# design.net
KiCad netlist of a schematic drawn in Altium Designer
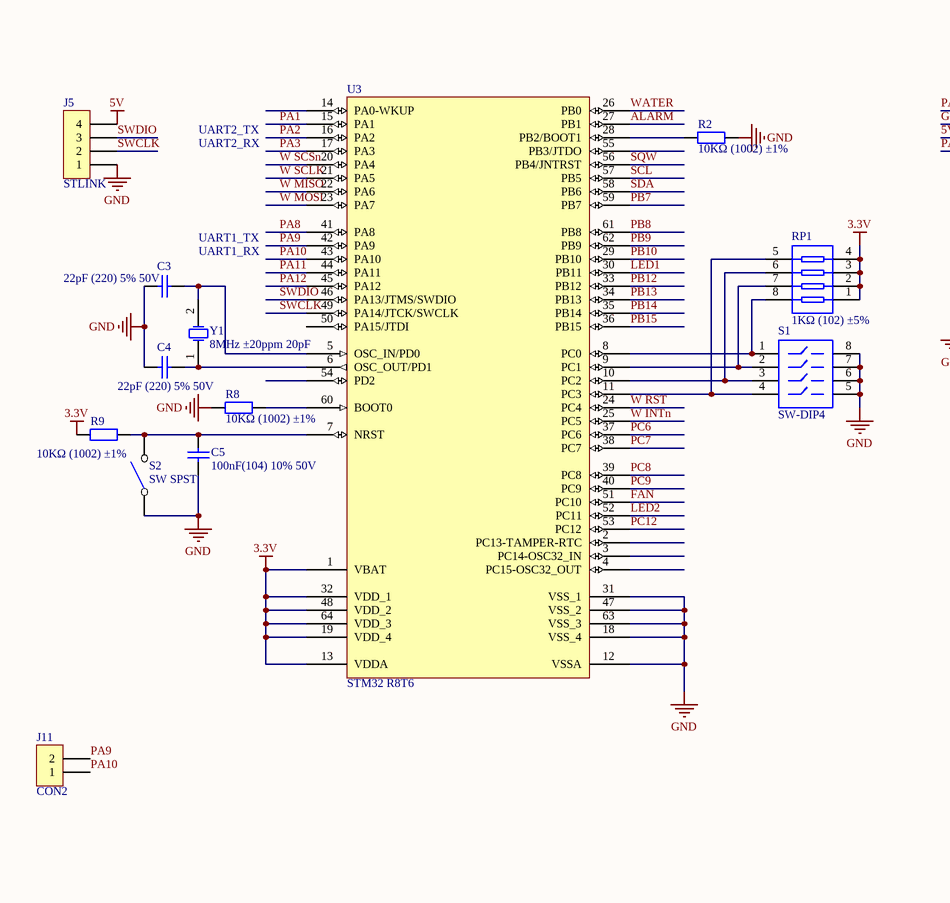
[diagram p0: 控制器.SchDoc, left]
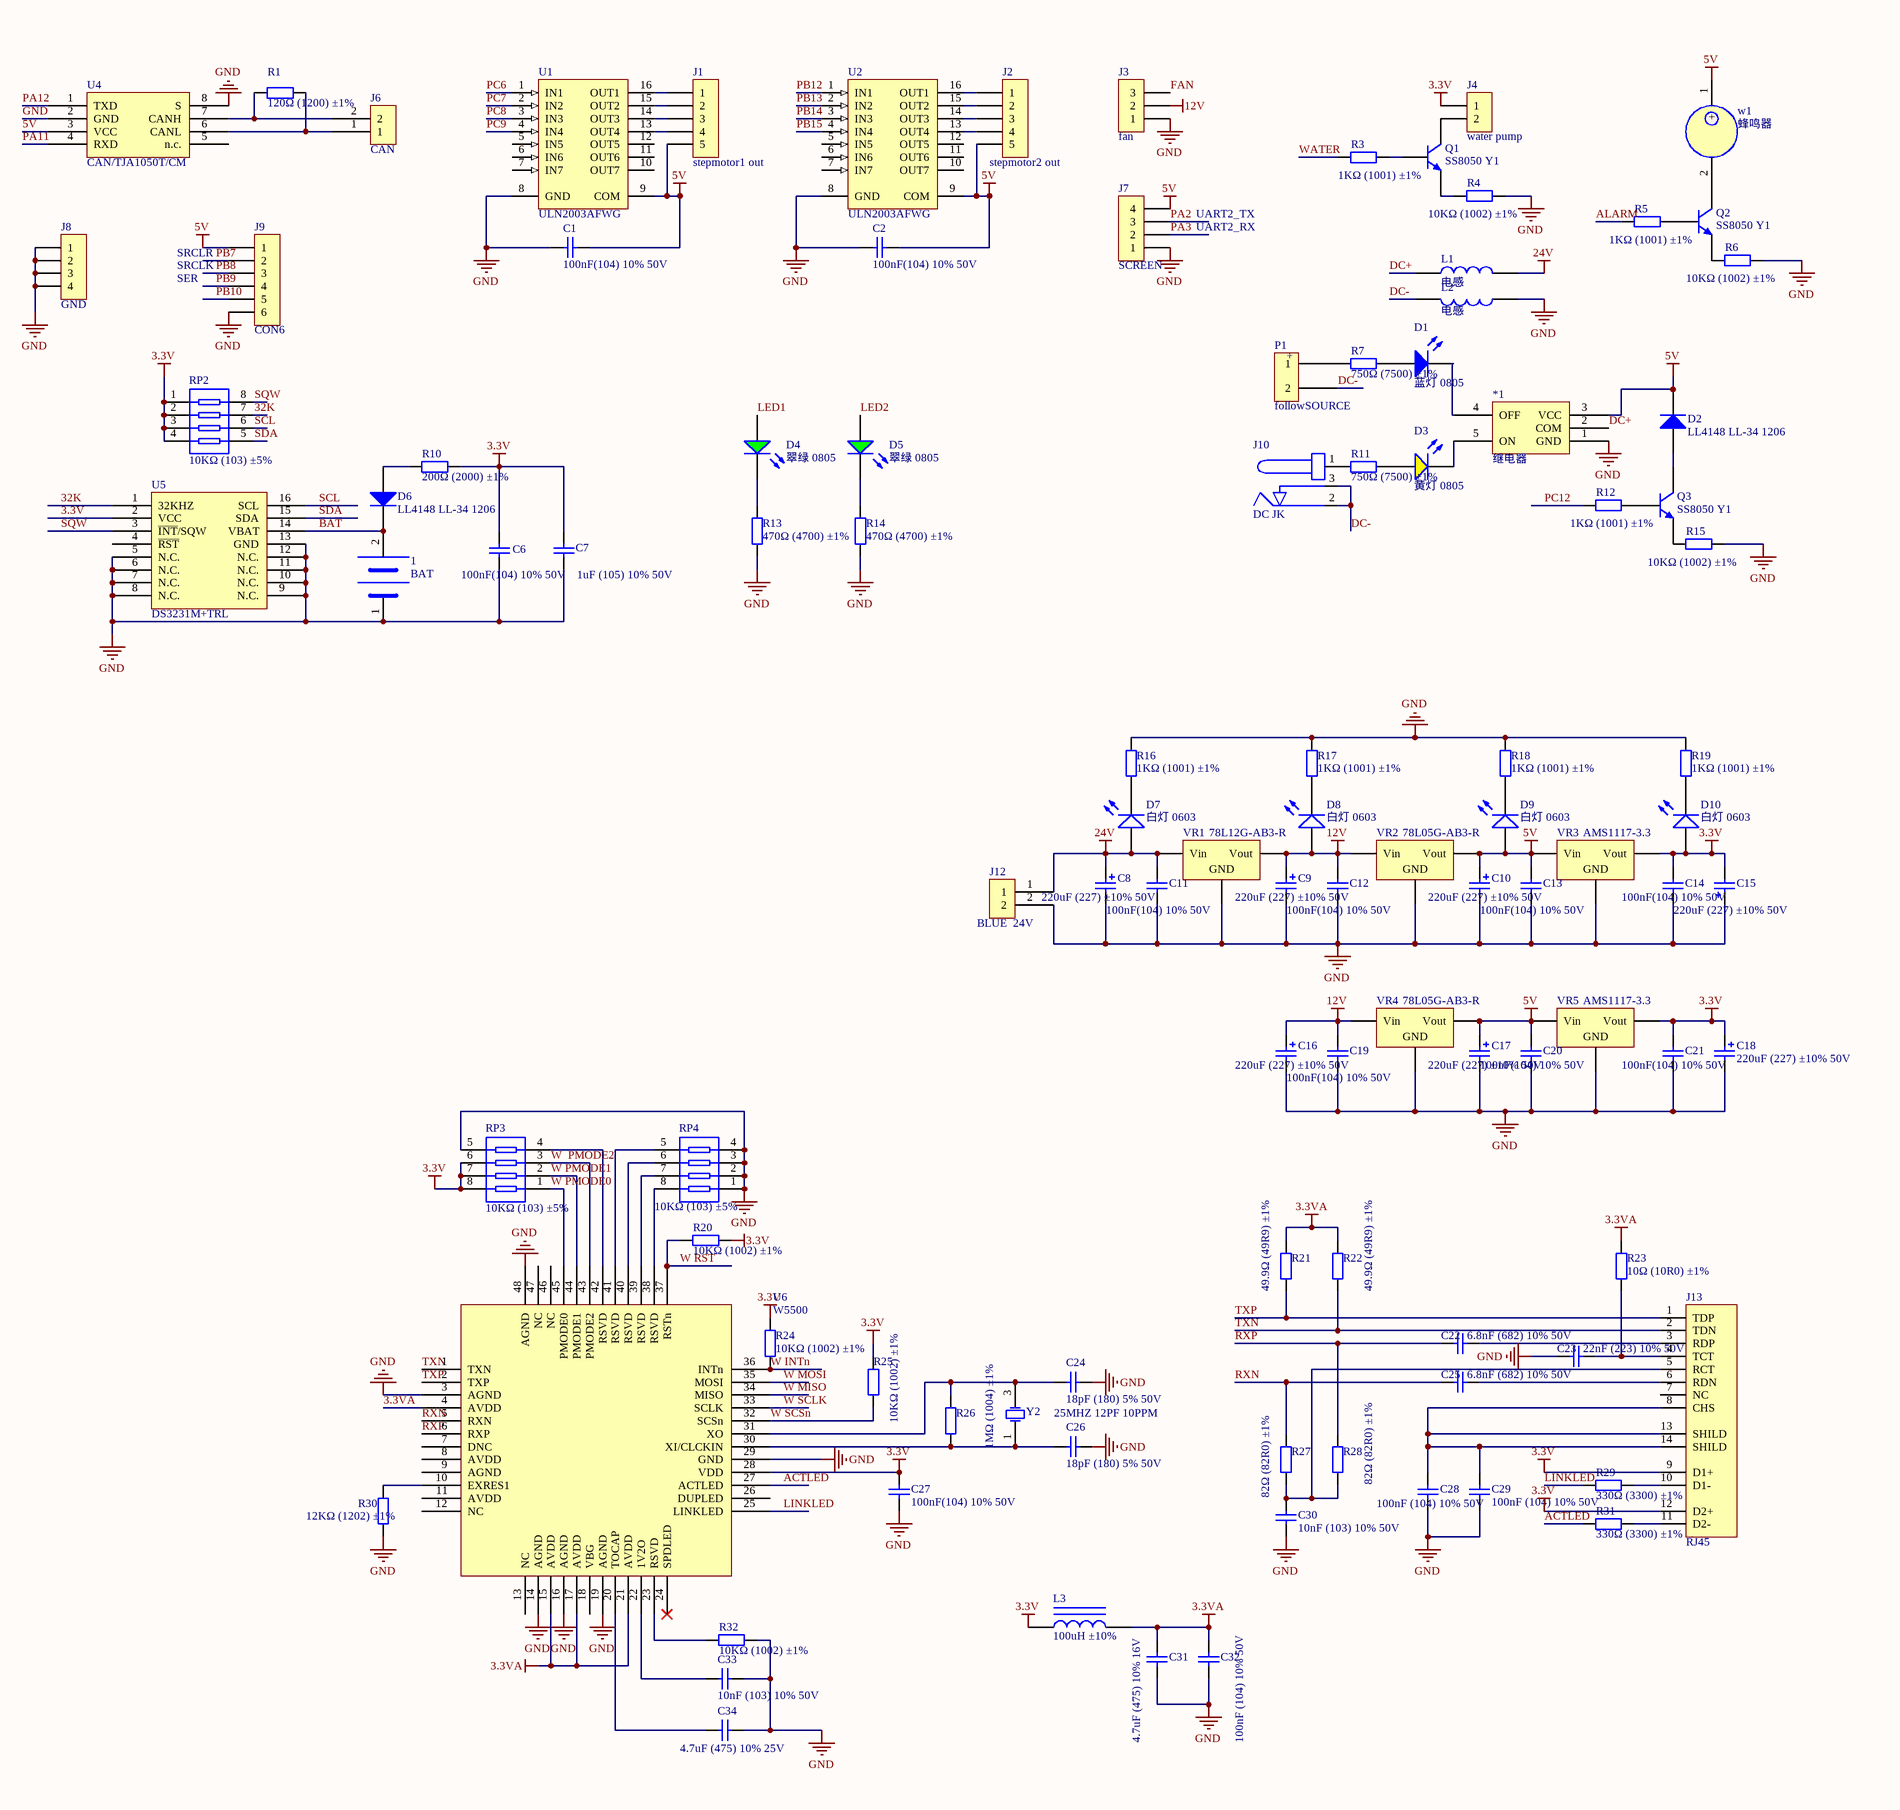
[diagram p1: 控制器.SchDoc, right]

(export (version "E")
  (design (tool "Eeschema 10.0.6"))
  (components
    (comp (ref "*1") (value "继电器") (footprint "RLY-964") (libsource (lib "毕设原理图封装库") (part "继电器")))
    (comp (ref "1") (value "BAT") (footprint "BAT") (libsource (lib "毕设原理图封装库") (part "BAT")))
    (comp (ref "C1")
      (value "100nF(104) 10% 50V")
      (footprint "LC-0805_C")
      (description "贴片电容")
      (libsource (lib "Miscellaneous Devices LC") (part "0805 100nF(104) 10% 50V"))
    )
    (comp (ref "C2")
      (value "100nF(104) 10% 50V")
      (footprint "LC-0805_C")
      (description "贴片电容")
      (libsource (lib "Miscellaneous Devices LC") (part "0805 100nF(104) 10% 50V"))
    )
    (comp (ref "C3")
      (value "22pF (220) 5% 50V")
      (footprint "LC-0805_C")
      (description "贴片电容")
      (libsource (lib "Miscellaneous Devices LC") (part "0805 22pF (220) 5% 50V"))
    )
    (comp (ref "C4")
      (value "22pF (220) 5% 50V")
      (footprint "LC-0805_C")
      (description "贴片电容")
      (libsource (lib "Miscellaneous Devices LC") (part "0805 22pF (220) 5% 50V"))
    )
    (comp (ref "C5")
      (value "100nF(104) 10% 50V")
      (footprint "LC-0805_C")
      (description "贴片电容")
      (libsource (lib "Miscellaneous Devices LC") (part "0805 100nF(104) 10% 50V"))
    )
    (comp (ref "C6")
      (value "100nF(104) 10% 50V")
      (footprint "LC-0805_C")
      (description "贴片电容")
      (libsource (lib "Miscellaneous Devices LC") (part "0805 100nF(104) 10% 50V"))
    )
    (comp (ref "C7")
      (value "1uF (105) 10% 50V")
      (footprint "LC-0805_C")
      (description "贴片电容")
      (libsource (lib "Miscellaneous Devices LC") (part "0805 1uF (105) 10% 50V"))
    )
    (comp (ref "C8")
      (value "220uF (227) ±10% 50V")
      (footprint "LC-CASE-B_3528")
      (description "钽电容")
      (libsource (lib "Miscellaneous Devices LC") (part "3528 100uF (107) 10% 6.3V"))
    )
    (comp (ref "C9")
      (value "220uF (227) ±10% 50V")
      (footprint "LC-CASE-B_3528")
      (description "钽电容")
      (libsource (lib "Miscellaneous Devices LC") (part "3528 100uF (107) 10% 6.3V"))
    )
    (comp (ref "C10")
      (value "220uF (227) ±10% 50V")
      (footprint "LC-CASE-B_3528")
      (description "钽电容")
      (libsource (lib "Miscellaneous Devices LC") (part "3528 100uF (107) 10% 6.3V"))
    )
    (comp (ref "C11")
      (value "100nF(104) 10% 50V")
      (footprint "LC-0805_C")
      (description "贴片电容")
      (libsource (lib "Miscellaneous Devices LC") (part "0805 100nF(104) 10% 50V"))
    )
    (comp (ref "C12")
      (value "100nF(104) 10% 50V")
      (footprint "LC-0805_C")
      (description "贴片电容")
      (libsource (lib "Miscellaneous Devices LC") (part "0805 100nF(104) 10% 50V"))
    )
    (comp (ref "C13")
      (value "100nF(104) 10% 50V")
      (footprint "LC-0805_C")
      (description "贴片电容")
      (libsource (lib "Miscellaneous Devices LC") (part "0805 100nF(104) 10% 50V"))
    )
    (comp (ref "C14")
      (value "100nF(104) 10% 50V")
      (footprint "LC-0805_C")
      (description "贴片电容")
      (libsource (lib "Miscellaneous Devices LC") (part "0805 100nF(104) 10% 50V"))
    )
    (comp (ref "C15")
      (value "220uF (227) ±10% 50V")
      (footprint "LC-CASE-B_3528")
      (description "钽电容")
      (libsource (lib "Miscellaneous Devices LC") (part "3528 100uF (107) 10% 6.3V"))
    )
    (comp (ref "C16")
      (value "220uF (227) ±10% 50V")
      (footprint "LC-CASE-B_3528")
      (description "钽电容")
      (libsource (lib "Miscellaneous Devices LC") (part "3528 100uF (107) 10% 6.3V"))
    )
    (comp (ref "C17")
      (value "220uF (227) ±10% 50V")
      (footprint "LC-CASE-B_3528")
      (description "钽电容")
      (libsource (lib "Miscellaneous Devices LC") (part "3528 100uF (107) 10% 6.3V"))
    )
    (comp (ref "C18")
      (value "220uF (227) ±10% 50V")
      (footprint "LC-CASE-B_3528")
      (description "钽电容")
      (libsource (lib "") (part "3528 100uF (107) 10% 6.3V_1"))
    )
    (comp (ref "C19")
      (value "100nF(104) 10% 50V")
      (footprint "LC-0805_C")
      (description "贴片电容")
      (libsource (lib "Miscellaneous Devices LC") (part "0805 100nF(104) 10% 50V"))
    )
    (comp (ref "C20")
      (value "100nF(104) 10% 50V")
      (footprint "LC-0805_C")
      (description "贴片电容")
      (libsource (lib "Miscellaneous Devices LC") (part "0805 100nF(104) 10% 50V"))
    )
    (comp (ref "C21")
      (value "100nF(104) 10% 50V")
      (footprint "LC-0805_C")
      (description "贴片电容")
      (libsource (lib "Miscellaneous Devices LC") (part "0805 100nF(104) 10% 50V"))
    )
    (comp (ref "C22")
      (value "6.8nF (682) 10% 50V")
      (footprint "LC-0603_C")
      (description "贴片电容")
      (libsource (lib "Miscellaneous Devices LC") (part "0603 6.8nF (682) 10% 50V"))
    )
    (comp (ref "C23")
      (value "22nF (223) 10% 50V")
      (footprint "LC-0603_C")
      (description "贴片电容")
      (libsource (lib "Miscellaneous Devices LC") (part "0603 22nF (223) 10% 50V"))
    )
    (comp (ref "C24")
      (value "18pF (180) 5% 50V")
      (footprint "LC-0805_C")
      (description "贴片电容")
      (libsource (lib "Miscellaneous Devices LC") (part "0805 18pF (180) 5% 50V"))
    )
    (comp (ref "C25")
      (value "6.8nF (682) 10% 50V")
      (footprint "LC-0603_C")
      (description "贴片电容")
      (libsource (lib "Miscellaneous Devices LC") (part "0603 6.8nF (682) 10% 50V"))
    )
    (comp (ref "C26")
      (value "18pF (180) 5% 50V")
      (footprint "LC-0805_C")
      (description "贴片电容")
      (libsource (lib "Miscellaneous Devices LC") (part "0805 18pF (180) 5% 50V"))
    )
    (comp (ref "C27")
      (value "100nF(104) 10% 50V")
      (footprint "LC-0805_C")
      (description "贴片电容")
      (libsource (lib "Miscellaneous Devices LC") (part "0805 100nF(104) 10% 50V"))
    )
    (comp (ref "C28")
      (value "100nF (104) 10% 50V")
      (footprint "LC-0603_C")
      (description "贴片电容")
      (libsource (lib "Miscellaneous Devices LC") (part "0603 100nF (104) 10% 50V"))
    )
    (comp (ref "C29")
      (value "100nF (104) 10% 50V")
      (footprint "LC-0603_C")
      (description "贴片电容")
      (libsource (lib "Miscellaneous Devices LC") (part "0603 100nF (104) 10% 50V"))
    )
    (comp (ref "C30")
      (value "10nF (103) 10% 50V")
      (footprint "LC-0603_C")
      (description "贴片电容")
      (libsource (lib "Miscellaneous Devices LC") (part "0603 10nF (103) 10% 50V"))
    )
    (comp (ref "C31")
      (value "4.7uF (475) 10% 16V")
      (footprint "LC-0603_C")
      (description "贴片电容")
      (libsource (lib "Miscellaneous Devices LC") (part "0603 4.7uF (475) 10% 16V"))
    )
    (comp (ref "C32")
      (value "100nF (104) 10% 50V")
      (footprint "LC-0603_C")
      (description "贴片电容")
      (libsource (lib "Miscellaneous Devices LC") (part "0603 100nF (104) 10% 50V"))
    )
    (comp (ref "C33")
      (value "10nF (103) 10% 50V")
      (footprint "LC-0805_C")
      (description "贴片电容")
      (libsource (lib "Miscellaneous Devices LC") (part "0805 10nF (103) 10% 50V"))
    )
    (comp (ref "C34")
      (value "4.7uF (475) 10% 25V")
      (footprint "LC-0805_C")
      (description "贴片电容")
      (libsource (lib "Miscellaneous Devices LC") (part "0805 4.7uF (475) 10% 25V"))
    )
    (comp (ref "D1")
      (value "蓝灯 0805")
      (footprint "LC-0805_LED_S1")
      (description "发光二极管")
      (libsource (lib "Miscellaneous Devices LC") (part "0805 蓝灯"))
    )
    (comp (ref "D2")
      (value "LL4148 LL-34 1206")
      (footprint "LC-LL-34")
      (description "开关二极管")
      (libsource (lib "Miscellaneous Devices LC") (part "LL-34 LL4148 LL-34 1206"))
    )
    (comp (ref "D3")
      (value "黄灯 0805")
      (footprint "LC-0805_LED_S1")
      (description "发光二极管")
      (libsource (lib "Miscellaneous Devices LC") (part "0805 黄灯"))
    )
    (comp (ref "D4")
      (value "翠绿 0805")
      (footprint "LC-0805_LED_S1")
      (description "发光二极管")
      (libsource (lib "Miscellaneous Devices LC") (part "0805 翠绿"))
    )
    (comp (ref "D5")
      (value "翠绿 0805")
      (footprint "LC-0805_LED_S1")
      (description "发光二极管")
      (libsource (lib "Miscellaneous Devices LC") (part "0805 翠绿"))
    )
    (comp (ref "D6")
      (value "LL4148 LL-34 1206")
      (footprint "LC-LL-34")
      (description "开关二极管")
      (libsource (lib "Miscellaneous Devices LC") (part "LL-34 LL4148 LL-34 1206"))
    )
    (comp (ref "D7")
      (value "白灯 0603")
      (footprint "LC-0603_LED_S1")
      (description "发光二极管")
      (libsource (lib "Miscellaneous Devices LC") (part "0603 白灯"))
    )
    (comp (ref "D8")
      (value "白灯 0603")
      (footprint "LC-0603_LED_S1")
      (description "发光二极管")
      (libsource (lib "Miscellaneous Devices LC") (part "0603 白灯"))
    )
    (comp (ref "D9")
      (value "白灯 0603")
      (footprint "LC-0603_LED_S1")
      (description "发光二极管")
      (libsource (lib "Miscellaneous Devices LC") (part "0603 白灯"))
    )
    (comp (ref "D10")
      (value "白灯 0603")
      (footprint "LC-0603_LED_S1")
      (description "发光二极管")
      (libsource (lib "Miscellaneous Devices LC") (part "0603 白灯"))
    )
    (comp (ref "J1") (value "stepmotor1 out") (footprint "防反插乘5") (libsource (lib "原理图封装库") (part "CON5")))
    (comp (ref "J2") (value "stepmotor2 out") (footprint "防反插乘5") (libsource (lib "原理图封装库") (part "CON5")))
    (comp (ref "J3") (value "fan") (footprint "SIP3") (libsource (lib "原理图封装库") (part "CON3")))
    (comp (ref "J4") (value "water pump") (footprint "SIP2") (libsource (lib "原理图封装库") (part "CON2")))
    (comp (ref "J5") (value "STLINK") (footprint "SIP4") (libsource (lib "毕设原理图封装库") (part "CON4")))
    (comp (ref "J6") (value "CAN") (footprint "蓝端子") (libsource (lib "") (part "蓝端子_2")))
    (comp (ref "J7") (value "SCREEN") (footprint "SIP4") (libsource (lib "毕设原理图封装库") (part "CON4")))
    (comp (ref "J8") (value "GND") (footprint "SIP4") (libsource (lib "") (part "CON4_1")))
    (comp (ref "J9") (value "CON6") (footprint "SIP6") (libsource (lib "毕设原理图封装库") (part "CON6")))
    (comp (ref "J10") (value "DC JK") (footprint "DC") (libsource (lib "Backup of 耳机座") (part "DC JK")))
    (comp (ref "J11") (value "CON2") (footprint "SIP2") (libsource (lib "毕设原理图封装库") (part "CON2")))
    (comp (ref "J12") (value "BLUE  24V") (footprint "蓝端子") (libsource (lib "") (part "蓝端子_1")))
    (comp (ref "J13") (value "RJ45") (footprint "RJ-45_GBE") (libsource (lib "毕设原理图封装库") (part "RJ45")))
    (comp (ref "L1") (value "电感") (libsource (lib "毕设原理图封装库") (part "电感")))
    (comp (ref "L2") (value "电感") (libsource (lib "毕设原理图封装库") (part "电感")))
    (comp (ref "L3")
      (value "100uH ±10%")
      (footprint "LC-0805_L")
      (description "贴片电感")
      (libsource (lib "Miscellaneous Devices LC") (part "0805 100uH 10%"))
    )
    (comp (ref "P1") (value "followSOURCE") (footprint "蓝端子") (libsource (lib "毕设原理图封装库") (part "蓝端子")))
    (comp (ref "Q1")
      (value "SS8050 Y1")
      (footprint "LC-SOT-23(SOT-23-3)")
      (description "三极管")
      (libsource (lib "Miscellaneous Devices LC") (part "SOT-23 SS8050 Y1"))
    )
    (comp (ref "Q2")
      (value "SS8050 Y1")
      (footprint "LC-SOT-23(SOT-23-3)")
      (description "三极管")
      (libsource (lib "Miscellaneous Devices LC") (part "SOT-23 SS8050 Y1"))
    )
    (comp (ref "Q3")
      (value "SS8050 Y1")
      (footprint "LC-SOT-23(SOT-23-3)")
      (description "三极管")
      (libsource (lib "Miscellaneous Devices LC") (part "SOT-23 SS8050 Y1"))
    )
    (comp (ref "R1")
      (value "120Ω (1200) ±1%")
      (footprint "LC-0805_R")
      (description "贴片电阻")
      (libsource (lib "Miscellaneous Devices LC") (part "0805 120Ω (1200) 1%"))
    )
    (comp (ref "R2")
      (value "10KΩ (1002) ±1%")
      (footprint "LC-0805_R")
      (description "贴片电阻")
      (libsource (lib "Miscellaneous Devices LC") (part "0805 10KΩ (1002) 1%"))
    )
    (comp (ref "R3")
      (value "1KΩ (1001) ±1%")
      (footprint "LC-0805_R")
      (description "贴片电阻")
      (libsource (lib "Miscellaneous Devices LC") (part "0805 1KΩ (1001) 1%"))
    )
    (comp (ref "R4")
      (value "10KΩ (1002) ±1%")
      (footprint "LC-0805_R")
      (description "贴片电阻")
      (libsource (lib "Miscellaneous Devices LC") (part "0805 10KΩ (1002) 1%"))
    )
    (comp (ref "R5")
      (value "1KΩ (1001) ±1%")
      (footprint "LC-0805_R")
      (description "贴片电阻")
      (libsource (lib "Miscellaneous Devices LC") (part "0805 1KΩ (1001) 1%"))
    )
    (comp (ref "R6")
      (value "10KΩ (1002) ±1%")
      (footprint "LC-0805_R")
      (description "贴片电阻")
      (libsource (lib "Miscellaneous Devices LC") (part "0805 10KΩ (1002) 1%"))
    )
    (comp (ref "R7")
      (value "750Ω (7500) ±1%")
      (footprint "LC-0805_R")
      (description "贴片电阻")
      (libsource (lib "Miscellaneous Devices LC") (part "0805 750Ω (7500) 1%"))
    )
    (comp (ref "R8")
      (value "10KΩ (1002) ±1%")
      (footprint "LC-0805_R")
      (description "贴片电阻")
      (libsource (lib "Miscellaneous Devices LC") (part "0805 10KΩ (1002) 1%"))
    )
    (comp (ref "R9")
      (value "10KΩ (1002) ±1%")
      (footprint "LC-0805_R")
      (description "贴片电阻")
      (libsource (lib "Miscellaneous Devices LC") (part "0805 10KΩ (1002) 1%"))
    )
    (comp (ref "R10")
      (value "200Ω (2000) ±1%")
      (footprint "LC-0805_R")
      (description "贴片电阻")
      (libsource (lib "Miscellaneous Devices LC") (part "0805 200Ω (2000) 1%"))
    )
    (comp (ref "R11")
      (value "750Ω (7500) ±1%")
      (footprint "LC-0805_R")
      (description "贴片电阻")
      (libsource (lib "Miscellaneous Devices LC") (part "0805 750Ω (7500) 1%"))
    )
    (comp (ref "R12")
      (value "1KΩ (1001) ±1%")
      (footprint "LC-0805_R")
      (description "贴片电阻")
      (libsource (lib "Miscellaneous Devices LC") (part "0805 1KΩ (1001) 1%"))
    )
    (comp (ref "R13")
      (value "470Ω (4700) ±1%")
      (footprint "LC-0805_R")
      (description "贴片电阻")
      (libsource (lib "Miscellaneous Devices LC") (part "0805 470Ω (4700) 1%"))
    )
    (comp (ref "R14")
      (value "470Ω (4700) ±1%")
      (footprint "LC-0805_R")
      (description "贴片电阻")
      (libsource (lib "Miscellaneous Devices LC") (part "0805 470Ω (4700) 1%"))
    )
    (comp (ref "R15")
      (value "10KΩ (1002) ±1%")
      (footprint "LC-0805_R")
      (description "贴片电阻")
      (libsource (lib "Miscellaneous Devices LC") (part "0805 10KΩ (1002) 1%"))
    )
    (comp (ref "R16")
      (value "1KΩ (1001) ±1%")
      (footprint "LC-0603_R")
      (description "贴片电阻")
      (libsource (lib "Miscellaneous Devices LC") (part "0603 1KΩ (1001) 1%"))
    )
    (comp (ref "R17")
      (value "1KΩ (1001) ±1%")
      (footprint "LC-0603_R")
      (description "贴片电阻")
      (libsource (lib "Miscellaneous Devices LC") (part "0603 1KΩ (1001) 1%"))
    )
    (comp (ref "R18")
      (value "1KΩ (1001) ±1%")
      (footprint "LC-0603_R")
      (description "贴片电阻")
      (libsource (lib "Miscellaneous Devices LC") (part "0603 1KΩ (1001) 1%"))
    )
    (comp (ref "R19")
      (value "1KΩ (1001) ±1%")
      (footprint "LC-0603_R")
      (description "贴片电阻")
      (libsource (lib "Miscellaneous Devices LC") (part "0603 1KΩ (1001) 1%"))
    )
    (comp (ref "R20")
      (value "10KΩ (1002) ±1%")
      (footprint "LC-0805_R")
      (description "贴片电阻")
      (libsource (lib "Miscellaneous Devices LC") (part "0805 10KΩ (1002) 1%"))
    )
    (comp (ref "R21")
      (value "49.9Ω (49R9) ±1%")
      (footprint "LC-0603_R")
      (description "贴片电阻")
      (libsource (lib "Miscellaneous Devices LC") (part "0603 49.9Ω (49R9) 1%"))
    )
    (comp (ref "R22")
      (value "49.9Ω (49R9) ±1%")
      (footprint "LC-0603_R")
      (description "贴片电阻")
      (libsource (lib "Miscellaneous Devices LC") (part "0603 49.9Ω (49R9) 1%"))
    )
    (comp (ref "R23")
      (value "10Ω (10R0) ±1%")
      (footprint "LC-0805_R")
      (description "贴片电阻")
      (libsource (lib "Miscellaneous Devices LC") (part "0805 10Ω (10R0) 1%"))
    )
    (comp (ref "R24")
      (value "10KΩ (1002) ±1%")
      (footprint "LC-0805_R")
      (description "贴片电阻")
      (libsource (lib "") (part "0805 10KΩ (1002) 1%_1"))
    )
    (comp (ref "R25")
      (value "10KΩ (1002) ±1%")
      (footprint "LC-0805_R")
      (description "贴片电阻")
      (libsource (lib "") (part "0805 10KΩ (1002) 1%_1"))
    )
    (comp (ref "R26")
      (value "1MΩ (1004) ±1%")
      (footprint "LC-0805_R")
      (description "贴片电阻")
      (libsource (lib "Miscellaneous Devices LC") (part "0805 1MΩ (1004) 1%"))
    )
    (comp (ref "R27")
      (value "82Ω (82R0) ±1%")
      (footprint "LC-0603_R")
      (description "贴片电阻")
      (libsource (lib "Miscellaneous Devices LC") (part "0603 82Ω (82R0) 1%"))
    )
    (comp (ref "R28")
      (value "82Ω (82R0) ±1%")
      (footprint "LC-0603_R")
      (description "贴片电阻")
      (libsource (lib "Miscellaneous Devices LC") (part "0603 82Ω (82R0) 1%"))
    )
    (comp (ref "R29")
      (value "330Ω (3300) ±1%")
      (footprint "LC-0603_R")
      (description "贴片电阻")
      (libsource (lib "Miscellaneous Devices LC") (part "0603 330Ω (3300) 1%"))
    )
    (comp (ref "R30")
      (value "12KΩ (1202) ±1%")
      (footprint "LC-0805_R")
      (description "贴片电阻")
      (libsource (lib "Miscellaneous Devices LC") (part "0805 12KΩ (1202) 1%"))
    )
    (comp (ref "R31")
      (value "330Ω (3300) ±1%")
      (footprint "LC-0603_R")
      (description "贴片电阻")
      (libsource (lib "Miscellaneous Devices LC") (part "0603 330Ω (3300) 1%"))
    )
    (comp (ref "R32")
      (value "10KΩ (1002) ±1%")
      (footprint "LC-0805_R")
      (description "贴片电阻")
      (libsource (lib "Miscellaneous Devices LC") (part "0805 10KΩ (1002) 1%"))
    )
    (comp (ref "RP1")
      (value "1KΩ (102) ±5%")
      (footprint "LC-0603_Rx4")
      (description "贴片排阻")
      (libsource (lib "Miscellaneous Devices LC") (part "0603*4  1KΩ (102) 5%"))
    )
    (comp (ref "RP2")
      (value "10KΩ (103) ±5%")
      (footprint "LC-0603_Rx4")
      (description "贴片排阻")
      (libsource (lib "Miscellaneous Devices LC") (part "0603*4  10KΩ (103) 5%"))
    )
    (comp (ref "RP3")
      (value "10KΩ (103) ±5%")
      (footprint "LC-0603_Rx4")
      (description "贴片排阻")
      (libsource (lib "Miscellaneous Devices LC") (part "0603*4  10KΩ (103) 5%"))
    )
    (comp (ref "RP4")
      (value "10KΩ (103) ±5%")
      (footprint "LC-0603_Rx4")
      (description "贴片排阻")
      (libsource (lib "Miscellaneous Devices LC") (part "0603*4  10KΩ (103) 5%"))
    )
    (comp (ref "S1")
      (value "SW-DIP4")
      (footprint "4位拨码开关")
      (description "4位拨码开关")
      (libsource (lib "毕设原理图封装库") (part "SW-DIP4"))
    )
    (comp (ref "S2")
      (value "SW SPST")
      (footprint "单片机小按键")
      (description "单刀单掷开关")
      (libsource (lib "毕设原理图封装库") (part "SW SPST"))
    )
    (comp (ref "U1")
      (value "ULN2003AFWG")
      (footprint "LC-SOIC-16_150mil")
      (description "大电流驱动")
      (libsource (lib "Miscellaneous Devices LC") (part "ULN2003AFWG"))
    )
    (comp (ref "U2")
      (value "ULN2003AFWG")
      (footprint "LC-SOIC-16_150mil")
      (description "大电流驱动")
      (libsource (lib "Miscellaneous Devices LC") (part "ULN2003AFWG"))
    )
    (comp (ref "U3")
      (value "STM32 R8T6")
      (footprint "LC-LQFP-64_10x10x05P")
      (libsource (lib "毕设原理图封装库") (part "STM32 R8T6"))
    )
    (comp (ref "U4")
      (value "CAN/TJA1050T/CM")
      (footprint "LC-SOIC-8_150mil")
      (description "CAN")
      (libsource (lib "Miscellaneous Devices LC") (part "CAN/TJA1050T/CM"))
    )
    (comp (ref "U5")
      (value "DS3231M+TRL")
      (footprint "LC-SOIC-16_300mil")
      (description "实时时钟")
      (libsource (lib "Miscellaneous Devices LC") (part "DS3231M+TRL"))
    )
    (comp (ref "U6")
      (value "W5500")
      (footprint "LC-LQFP-48_7x7x05P")
      (description "以太网")
      (libsource (lib "Miscellaneous Devices LC") (part "W5500"))
    )
    (comp (ref "VR1")
      (value "78L12G-AB3-R")
      (footprint "LC-SOT-89(SOT-89-3)")
      (description "低压差线性稳压(LDO)")
      (libsource (lib "Miscellaneous Devices LC") (part "SOT-89 78L12G-AB3-R"))
    )
    (comp (ref "VR2")
      (value "78L05G-AB3-R")
      (footprint "LC-SOT-89(SOT-89-3)")
      (description "低压差线性稳压(LDO)")
      (libsource (lib "Miscellaneous Devices LC") (part "SOT-89 78L05G-AB3-R"))
    )
    (comp (ref "VR3")
      (value "AMS1117-3.3")
      (footprint "LC-SOT-223")
      (description "低压差线性稳压(LDO)")
      (libsource (lib "Miscellaneous Devices LC") (part "SOT-223 AMS1117-3.3"))
    )
    (comp (ref "VR4")
      (value "78L05G-AB3-R")
      (footprint "LC-SOT-89(SOT-89-3)")
      (description "低压差线性稳压(LDO)")
      (libsource (lib "Miscellaneous Devices LC") (part "SOT-89 78L05G-AB3-R"))
    )
    (comp (ref "VR5")
      (value "AMS1117-3.3")
      (footprint "LC-SOT-223")
      (description "低压差线性稳压(LDO)")
      (libsource (lib "Miscellaneous Devices LC") (part "SOT-223 AMS1117-3.3"))
    )
    (comp (ref "w1") (value "蜂鸣器") (footprint "蜂鸣器") (libsource (lib "毕设原理图封装库") (part "蜂鸣器")))
    (comp (ref "Y1")
      (value "8MHz ±20ppm 20pF")
      (footprint "LC-SMD-5032_2P")
      (description "贴片晶振")
      (libsource (lib "Miscellaneous Devices LC") (part "SMD-5032_2P 8MHz 20ppm 20pF"))
    )
    (comp (ref "Y2")
      (value "25MHZ 12PF 10PPM")
      (footprint "LC-SMD-3225_4P")
      (description "贴片晶振")
      (libsource (lib "Miscellaneous Devices LC") (part "SMD-3225_4P  25MHZ 12PF 10PPM"))
    )
  )
  (nets
    (net (code "1") (name "/32K") (class "Default")
      (node (ref "RP2") (pin "7") (pinfunction "7_7") (pintype "passive"))
      (node (ref "U5") (pin "1") (pinfunction "32KHZ_1") (pintype "passive"))
    )
    (net (code "2") (name "/ACTLED") (class "Default")
      (node (ref "R31") (pin "1") (pinfunction "1_1") (pintype "passive"))
      (node (ref "U6") (pin "27") (pinfunction "ACTLED_27") (pintype "passive"))
    )
    (net (code "3") (name "/ALARM") (class "Default")
      (node (ref "R5") (pin "1") (pinfunction "1_1") (pintype "passive"))
      (node (ref "U3") (pin "27") (pinfunction "PB1_27") (pintype "bidirectional"))
    )
    (net (code "4") (name "/BAT") (class "Default")
      (node (ref "1") (pin "2") (pinfunction "2_2") (pintype "passive"))
      (node (ref "D6") (pin "2") (pinfunction "K_2") (pintype "passive"))
      (node (ref "U5") (pin "14") (pinfunction "VBAT_14") (pintype "passive"))
    )
    (net (code "5") (name "/DC+") (class "Default")
      (node (ref "*1") (pin "2") (pinfunction "COM_2") (pintype "passive"))
      (node (ref "L1") (pin "1") (pinfunction "1_1") (pintype "passive"))
    )
    (net (code "6") (name "/DC-") (class "Default")
      (node (ref "J10") (pin "2") (pinfunction "GND_2") (pintype "passive"))
      (node (ref "J10") (pin "3") (pinfunction "GND_3") (pintype "passive"))
      (node (ref "L2") (pin "2") (pinfunction "2_2") (pintype "passive"))
      (node (ref "P1") (pin "2") (pinfunction "2_2") (pintype "passive"))
    )
    (net (code "7") (name "/FAN") (class "Default")
      (node (ref "J3") (pin "3") (pinfunction "3_3") (pintype "passive"))
      (node (ref "U3") (pin "51") (pinfunction "PC10_51") (pintype "bidirectional"))
    )
    (net (code "8") (name "/LED1") (class "Default")
      (node (ref "D4") (pin "A") (pinfunction "A_A") (pintype "passive"))
      (node (ref "U3") (pin "30") (pinfunction "PB11_30") (pintype "bidirectional"))
    )
    (net (code "9") (name "/LED2") (class "Default")
      (node (ref "D5") (pin "A") (pinfunction "A_A") (pintype "passive"))
      (node (ref "U3") (pin "52") (pinfunction "PC11_52") (pintype "bidirectional"))
    )
    (net (code "10") (name "/LINKLED") (class "Default")
      (node (ref "R29") (pin "1") (pinfunction "1_1") (pintype "passive"))
      (node (ref "U6") (pin "25") (pinfunction "LINKLED_25") (pintype "passive"))
    )
    (net (code "11") (name "/PA1") (class "Default")
      (node (ref "U3") (pin "15") (pinfunction "PA1_15") (pintype "bidirectional"))
    )
    (net (code "12") (name "/PA2") (class "Default")
      (node (ref "J7") (pin "3") (pinfunction "3_3") (pintype "passive"))
      (node (ref "U3") (pin "16") (pinfunction "PA2_16") (pintype "bidirectional"))
    )
    (net (code "13") (name "/PA3") (class "Default")
      (node (ref "J7") (pin "2") (pinfunction "2_2") (pintype "passive"))
      (node (ref "U3") (pin "17") (pinfunction "PA3_17") (pintype "bidirectional"))
    )
    (net (code "14") (name "/PA8") (class "Default")
      (node (ref "U3") (pin "41") (pinfunction "PA8_41") (pintype "bidirectional"))
    )
    (net (code "15") (name "/PA9") (class "Default")
      (node (ref "J11") (pin "2") (pinfunction "2_2") (pintype "passive"))
      (node (ref "U3") (pin "42") (pinfunction "PA9_42") (pintype "bidirectional"))
    )
    (net (code "16") (name "/PA10") (class "Default")
      (node (ref "J11") (pin "1") (pinfunction "1_1") (pintype "passive"))
      (node (ref "U3") (pin "43") (pinfunction "PA10_43") (pintype "bidirectional"))
    )
    (net (code "17") (name "/PA11") (class "Default")
      (node (ref "U3") (pin "44") (pinfunction "PA11_44") (pintype "bidirectional"))
      (node (ref "U4") (pin "4") (pinfunction "RXD_4") (pintype "passive"))
    )
    (net (code "18") (name "/PA12") (class "Default")
      (node (ref "U3") (pin "45") (pinfunction "PA12_45") (pintype "bidirectional"))
      (node (ref "U4") (pin "1") (pinfunction "TXD_1") (pintype "passive"))
    )
    (net (code "19") (name "/PB7") (class "Default")
      (node (ref "J9") (pin "2") (pinfunction "2_2") (pintype "passive"))
      (node (ref "U3") (pin "59") (pinfunction "PB7_59") (pintype "bidirectional"))
    )
    (net (code "20") (name "/PB8") (class "Default")
      (node (ref "J9") (pin "3") (pinfunction "3_3") (pintype "passive"))
      (node (ref "U3") (pin "61") (pinfunction "PB8_61") (pintype "bidirectional"))
    )
    (net (code "21") (name "/PB9") (class "Default")
      (node (ref "J9") (pin "4") (pinfunction "4_4") (pintype "passive"))
      (node (ref "U3") (pin "62") (pinfunction "PB9_62") (pintype "bidirectional"))
    )
    (net (code "22") (name "/PB10") (class "Default")
      (node (ref "J9") (pin "5") (pinfunction "5_5") (pintype "passive"))
      (node (ref "U3") (pin "29") (pinfunction "PB10_29") (pintype "bidirectional"))
    )
    (net (code "23") (name "/PB12") (class "Default")
      (node (ref "U2") (pin "1") (pinfunction "IN1_1") (pintype "input"))
      (node (ref "U3") (pin "33") (pinfunction "PB12_33") (pintype "bidirectional"))
    )
    (net (code "24") (name "/PB13") (class "Default")
      (node (ref "U2") (pin "2") (pinfunction "IN2_2") (pintype "input"))
      (node (ref "U3") (pin "34") (pinfunction "PB13_34") (pintype "bidirectional"))
    )
    (net (code "25") (name "/PB14") (class "Default")
      (node (ref "U2") (pin "3") (pinfunction "IN3_3") (pintype "input"))
      (node (ref "U3") (pin "35") (pinfunction "PB14_35") (pintype "bidirectional"))
    )
    (net (code "26") (name "/PB15") (class "Default")
      (node (ref "U2") (pin "4") (pinfunction "IN4_4") (pintype "input"))
      (node (ref "U3") (pin "36") (pinfunction "PB15_36") (pintype "bidirectional"))
    )
    (net (code "27") (name "/PC6") (class "Default")
      (node (ref "U1") (pin "1") (pinfunction "IN1_1") (pintype "input"))
      (node (ref "U3") (pin "37") (pinfunction "PC6_37") (pintype "bidirectional"))
    )
    (net (code "28") (name "/PC7") (class "Default")
      (node (ref "U1") (pin "2") (pinfunction "IN2_2") (pintype "input"))
      (node (ref "U3") (pin "38") (pinfunction "PC7_38") (pintype "bidirectional"))
    )
    (net (code "29") (name "/PC8") (class "Default")
      (node (ref "U1") (pin "3") (pinfunction "IN3_3") (pintype "input"))
      (node (ref "U3") (pin "39") (pinfunction "PC8_39") (pintype "bidirectional"))
    )
    (net (code "30") (name "/PC9") (class "Default")
      (node (ref "U1") (pin "4") (pinfunction "IN4_4") (pintype "input"))
      (node (ref "U3") (pin "40") (pinfunction "PC9_40") (pintype "bidirectional"))
    )
    (net (code "31") (name "/PC12") (class "Default")
      (node (ref "R12") (pin "1") (pinfunction "1_1") (pintype "passive"))
      (node (ref "U3") (pin "53") (pinfunction "PC12_53") (pintype "bidirectional"))
    )
    (net (code "32") (name "/RXN") (class "Default")
      (node (ref "C25") (pin "1") (pinfunction "1_1") (pintype "passive"))
      (node (ref "R27") (pin "2") (pinfunction "2_2") (pintype "passive"))
      (node (ref "U6") (pin "5") (pinfunction "RXN_5") (pintype "passive"))
    )
    (net (code "33") (name "/RXP") (class "Default")
      (node (ref "C22") (pin "1") (pinfunction "1_1") (pintype "passive"))
      (node (ref "R28") (pin "2") (pinfunction "2_2") (pintype "passive"))
      (node (ref "U6") (pin "6") (pinfunction "RXP_6") (pintype "passive"))
    )
    (net (code "34") (name "/SCL") (class "Default")
      (node (ref "RP2") (pin "6") (pinfunction "6_6") (pintype "passive"))
      (node (ref "U3") (pin "57") (pinfunction "PB5_57") (pintype "bidirectional"))
      (node (ref "U5") (pin "16") (pinfunction "SCL_16") (pintype "passive"))
    )
    (net (code "35") (name "/SDA") (class "Default")
      (node (ref "RP2") (pin "5") (pinfunction "5_5") (pintype "passive"))
      (node (ref "U3") (pin "58") (pinfunction "PB6_58") (pintype "bidirectional"))
      (node (ref "U5") (pin "15") (pinfunction "SDA_15") (pintype "passive"))
    )
    (net (code "36") (name "/SQW") (class "Default")
      (node (ref "RP2") (pin "8") (pinfunction "8_8") (pintype "passive"))
      (node (ref "U3") (pin "56") (pinfunction "PB4/JNTRST_56") (pintype "bidirectional"))
      (node (ref "U5") (pin "3") (pinfunction "~{INT}/SQW_3") (pintype "passive"))
    )
    (net (code "37") (name "/SWCLK") (class "Default")
      (node (ref "J5") (pin "2") (pinfunction "2_2") (pintype "passive"))
      (node (ref "U3") (pin "49") (pinfunction "PA14/JTCK/SWCLK_49") (pintype "bidirectional"))
    )
    (net (code "38") (name "/SWDIO") (class "Default")
      (node (ref "J5") (pin "3") (pinfunction "3_3") (pintype "passive"))
      (node (ref "U3") (pin "46") (pinfunction "PA13/JTMS/SWDIO_46") (pintype "bidirectional"))
    )
    (net (code "39") (name "/TXN") (class "Default")
      (node (ref "J13") (pin "2") (pinfunction "TDN_2") (pintype "passive"))
      (node (ref "R22") (pin "1") (pinfunction "1_1") (pintype "passive"))
      (node (ref "U6") (pin "1") (pinfunction "TXN_1") (pintype "passive"))
    )
    (net (code "40") (name "/TXP") (class "Default")
      (node (ref "J13") (pin "1") (pinfunction "TDP_1") (pintype "passive"))
      (node (ref "R21") (pin "1") (pinfunction "1_1") (pintype "passive"))
      (node (ref "U6") (pin "2") (pinfunction "TXP_2") (pintype "passive"))
    )
    (net (code "41") (name "/W  PMODE2") (class "Default")
      (node (ref "RP3") (pin "3") (pinfunction "3_3") (pintype "passive"))
      (node (ref "U6") (pin "43") (pinfunction "PMODE2_43") (pintype "passive"))
    )
    (net (code "42") (name "/W INTn") (class "Default")
      (node (ref "R24") (pin "1") (pinfunction "1_1") (pintype "passive"))
      (node (ref "U3") (pin "25") (pinfunction "PC5_25") (pintype "bidirectional"))
      (node (ref "U6") (pin "36") (pinfunction "INTn_36") (pintype "passive"))
    )
    (net (code "43") (name "/W MISO") (class "Default")
      (node (ref "U3") (pin "22") (pinfunction "PA6_22") (pintype "bidirectional"))
      (node (ref "U6") (pin "34") (pinfunction "MISO_34") (pintype "passive"))
    )
    (net (code "44") (name "/W MOSI") (class "Default")
      (node (ref "U3") (pin "23") (pinfunction "PA7_23") (pintype "bidirectional"))
      (node (ref "U6") (pin "35") (pinfunction "MOSI_35") (pintype "passive"))
    )
    (net (code "45") (name "/W PMODE0") (class "Default")
      (node (ref "RP3") (pin "1") (pinfunction "1_1") (pintype "passive"))
      (node (ref "U6") (pin "45") (pinfunction "PMODE0_45") (pintype "passive"))
    )
    (net (code "46") (name "/W PMODE1") (class "Default")
      (node (ref "RP3") (pin "2") (pinfunction "2_2") (pintype "passive"))
      (node (ref "U6") (pin "44") (pinfunction "PMODE1_44") (pintype "passive"))
    )
    (net (code "47") (name "/W RST") (class "Default")
      (node (ref "R20") (pin "1") (pinfunction "1_1") (pintype "passive"))
      (node (ref "U3") (pin "24") (pinfunction "PC4_24") (pintype "bidirectional"))
      (node (ref "U6") (pin "37") (pinfunction "RSTn_37") (pintype "passive"))
    )
    (net (code "48") (name "/W SCLK") (class "Default")
      (node (ref "U3") (pin "21") (pinfunction "PA5_21") (pintype "bidirectional"))
      (node (ref "U6") (pin "33") (pinfunction "SCLK_33") (pintype "passive"))
    )
    (net (code "49") (name "/W SCSn") (class "Default")
      (node (ref "R25") (pin "1") (pinfunction "1_1") (pintype "passive"))
      (node (ref "U3") (pin "20") (pinfunction "PA4_20") (pintype "bidirectional"))
      (node (ref "U6") (pin "32") (pinfunction "SCSn_32") (pintype "passive"))
    )
    (net (code "50") (name "/WATER") (class "Default")
      (node (ref "R3") (pin "1") (pinfunction "1_1") (pintype "passive"))
      (node (ref "U3") (pin "26") (pinfunction "PB0_26") (pintype "bidirectional"))
    )
    (net (code "51") (name "3.3V") (class "Default")
      (node (ref "C14") (pin "1") (pinfunction "1_1") (pintype "passive"))
      (node (ref "C15") (pin "2") (pinfunction "2_2") (pintype "passive"))
      (node (ref "C18") (pin "2") (pinfunction "2_2") (pintype "passive"))
      (node (ref "C21") (pin "1") (pinfunction "1_1") (pintype "passive"))
      (node (ref "C27") (pin "2") (pinfunction "2_2") (pintype "passive"))
      (node (ref "C6") (pin "2") (pinfunction "2_2") (pintype "passive"))
      (node (ref "C7") (pin "2") (pinfunction "2_2") (pintype "passive"))
      (node (ref "D10") (pin "A") (pinfunction "A_A") (pintype "passive"))
      (node (ref "J13") (pin "12") (pinfunction "D2+_12") (pintype "passive"))
      (node (ref "J13") (pin "9") (pinfunction "D1+_9") (pintype "passive"))
      (node (ref "J4") (pin "1") (pinfunction "1_1") (pintype "passive"))
      (node (ref "L3") (pin "1") (pinfunction "1_1") (pintype "passive"))
      (node (ref "R10") (pin "1") (pinfunction "1_1") (pintype "passive"))
      (node (ref "R20") (pin "2") (pinfunction "2_2") (pintype "passive"))
      (node (ref "R24") (pin "2") (pinfunction "2_2") (pintype "passive"))
      (node (ref "R25") (pin "2") (pinfunction "2_2") (pintype "passive"))
      (node (ref "R9") (pin "1") (pinfunction "1_1") (pintype "passive"))
      (node (ref "RP1") (pin "1") (pinfunction "1_1") (pintype "passive"))
      (node (ref "RP1") (pin "2") (pinfunction "2_2") (pintype "passive"))
      (node (ref "RP1") (pin "3") (pinfunction "3_3") (pintype "passive"))
      (node (ref "RP1") (pin "4") (pinfunction "4_4") (pintype "passive"))
      (node (ref "RP2") (pin "1") (pinfunction "1_1") (pintype "passive"))
      (node (ref "RP2") (pin "2") (pinfunction "2_2") (pintype "passive"))
      (node (ref "RP2") (pin "3") (pinfunction "3_3") (pintype "passive"))
      (node (ref "RP2") (pin "4") (pinfunction "4_4") (pintype "passive"))
      (node (ref "RP3") (pin "6") (pinfunction "6_6") (pintype "passive"))
      (node (ref "RP3") (pin "7") (pinfunction "7_7") (pintype "passive"))
      (node (ref "RP3") (pin "8") (pinfunction "8_8") (pintype "passive"))
      (node (ref "U3") (pin "1") (pinfunction "VBAT_1") (pintype "power_in"))
      (node (ref "U3") (pin "13") (pinfunction "VDDA_13") (pintype "power_in"))
      (node (ref "U3") (pin "19") (pinfunction "VDD_4_19") (pintype "power_in"))
      (node (ref "U3") (pin "32") (pinfunction "VDD_1_32") (pintype "power_in"))
      (node (ref "U3") (pin "48") (pinfunction "VDD_2_48") (pintype "power_in"))
      (node (ref "U3") (pin "64") (pinfunction "VDD_3_64") (pintype "power_in"))
      (node (ref "U5") (pin "2") (pinfunction "VCC_2") (pintype "passive"))
      (node (ref "U6") (pin "28") (pinfunction "VDD_28") (pintype "passive"))
      (node (ref "VR3") (pin "2") (pinfunction "Vout_2") (pintype "passive"))
      (node (ref "VR5") (pin "2") (pinfunction "Vout_2") (pintype "passive"))
    )
    (net (code "52") (name "3.3VA") (class "Default")
      (node (ref "C31") (pin "2") (pinfunction "2_2") (pintype "passive"))
      (node (ref "C32") (pin "2") (pinfunction "2_2") (pintype "passive"))
      (node (ref "L3") (pin "2") (pinfunction "2_2") (pintype "passive"))
      (node (ref "R21") (pin "2") (pinfunction "2_2") (pintype "passive"))
      (node (ref "R22") (pin "2") (pinfunction "2_2") (pintype "passive"))
      (node (ref "R23") (pin "2") (pinfunction "2_2") (pintype "passive"))
      (node (ref "U6") (pin "15") (pinfunction "AVDD_15") (pintype "passive"))
      (node (ref "U6") (pin "17") (pinfunction "AVDD_17") (pintype "passive"))
      (node (ref "U6") (pin "21") (pinfunction "AVDD_21") (pintype "passive"))
      (node (ref "U6") (pin "4") (pinfunction "AVDD_4") (pintype "passive"))
    )
    (net (code "53") (name "5V") (class "Default")
      (node (ref "*1") (pin "3") (pinfunction "VCC_3") (pintype "passive"))
      (node (ref "C1") (pin "2") (pinfunction "2_2") (pintype "passive"))
      (node (ref "C10") (pin "1") (pinfunction "1_1") (pintype "passive"))
      (node (ref "C13") (pin "2") (pinfunction "2_2") (pintype "passive"))
      (node (ref "C17") (pin "1") (pinfunction "1_1") (pintype "passive"))
      (node (ref "C2") (pin "2") (pinfunction "2_2") (pintype "passive"))
      (node (ref "C20") (pin "1") (pinfunction "1_1") (pintype "passive"))
      (node (ref "D2") (pin "2") (pinfunction "K_2") (pintype "passive"))
      (node (ref "D9") (pin "A") (pinfunction "A_A") (pintype "passive"))
      (node (ref "J1") (pin "5") (pinfunction "5_5") (pintype "passive"))
      (node (ref "J2") (pin "5") (pinfunction "5_5") (pintype "passive"))
      (node (ref "J5") (pin "4") (pinfunction "4_4") (pintype "passive"))
      (node (ref "J7") (pin "4") (pinfunction "4_4") (pintype "passive"))
      (node (ref "J9") (pin "1") (pinfunction "1_1") (pintype "passive"))
      (node (ref "U1") (pin "9") (pinfunction "COM_9") (pintype "passive"))
      (node (ref "U2") (pin "9") (pinfunction "COM_9") (pintype "passive"))
      (node (ref "U4") (pin "3") (pinfunction "VCC_3") (pintype "passive"))
      (node (ref "VR2") (pin "3") (pinfunction "Vout_3") (pintype "passive"))
      (node (ref "VR3") (pin "3") (pinfunction "Vin_3") (pintype "passive"))
      (node (ref "VR4") (pin "3") (pinfunction "Vout_3") (pintype "passive"))
      (node (ref "VR5") (pin "3") (pinfunction "Vin_3") (pintype "passive"))
      (node (ref "w1") (pin "1") (pinfunction "+_1") (pintype "passive"))
    )
    (net (code "54") (name "12V") (class "Default")
      (node (ref "C12") (pin "2") (pinfunction "2_2") (pintype "passive"))
      (node (ref "C16") (pin "1") (pinfunction "1_1") (pintype "passive"))
      (node (ref "C19") (pin "2") (pinfunction "2_2") (pintype "passive"))
      (node (ref "C9") (pin "1") (pinfunction "1_1") (pintype "passive"))
      (node (ref "D8") (pin "A") (pinfunction "A_A") (pintype "passive"))
      (node (ref "J3") (pin "2") (pinfunction "2_2") (pintype "passive"))
      (node (ref "VR1") (pin "3") (pinfunction "Vout_3") (pintype "passive"))
      (node (ref "VR2") (pin "1") (pinfunction "Vin_1") (pintype "passive"))
      (node (ref "VR4") (pin "1") (pinfunction "Vin_1") (pintype "passive"))
    )
    (net (code "55") (name "24V") (class "Default")
      (node (ref "C11") (pin "2") (pinfunction "2_2") (pintype "passive"))
      (node (ref "C8") (pin "1") (pinfunction "1_1") (pintype "passive"))
      (node (ref "D7") (pin "A") (pinfunction "A_A") (pintype "passive"))
      (node (ref "J12") (pin "1") (pinfunction "1_1") (pintype "passive"))
      (node (ref "L1") (pin "2") (pinfunction "2_2") (pintype "passive"))
      (node (ref "VR1") (pin "1") (pinfunction "Vin_1") (pintype "passive"))
    )
    (net (code "56") (name "GND") (class "Default")
      (node (ref "*1") (pin "1") (pinfunction "GND_1") (pintype "passive"))
      (node (ref "1") (pin "1") (pinfunction "1_1") (pintype "passive"))
      (node (ref "C1") (pin "1") (pinfunction "1_1") (pintype "passive"))
      (node (ref "C10") (pin "2") (pinfunction "2_2") (pintype "passive"))
      (node (ref "C11") (pin "1") (pinfunction "1_1") (pintype "passive"))
      (node (ref "C12") (pin "1") (pinfunction "1_1") (pintype "passive"))
      (node (ref "C13") (pin "1") (pinfunction "1_1") (pintype "passive"))
      (node (ref "C14") (pin "2") (pinfunction "2_2") (pintype "passive"))
      (node (ref "C15") (pin "1") (pinfunction "1_1") (pintype "passive"))
      (node (ref "C16") (pin "2") (pinfunction "2_2") (pintype "passive"))
      (node (ref "C17") (pin "2") (pinfunction "2_2") (pintype "passive"))
      (node (ref "C18") (pin "2") (pinfunction "2_2") (pintype "passive"))
      (node (ref "C19") (pin "1") (pinfunction "1_1") (pintype "passive"))
      (node (ref "C2") (pin "1") (pinfunction "1_1") (pintype "passive"))
      (node (ref "C20") (pin "2") (pinfunction "2_2") (pintype "passive"))
      (node (ref "C21") (pin "2") (pinfunction "2_2") (pintype "passive"))
      (node (ref "C23") (pin "1") (pinfunction "1_1") (pintype "passive"))
      (node (ref "C24") (pin "2") (pinfunction "2_2") (pintype "passive"))
      (node (ref "C26") (pin "2") (pinfunction "2_2") (pintype "passive"))
      (node (ref "C27") (pin "1") (pinfunction "1_1") (pintype "passive"))
      (node (ref "C28") (pin "1") (pinfunction "1_1") (pintype "passive"))
      (node (ref "C29") (pin "1") (pinfunction "1_1") (pintype "passive"))
      (node (ref "C3") (pin "1") (pinfunction "1_1") (pintype "passive"))
      (node (ref "C30") (pin "1") (pinfunction "1_1") (pintype "passive"))
      (node (ref "C31") (pin "1") (pinfunction "1_1") (pintype "passive"))
      (node (ref "C32") (pin "1") (pinfunction "1_1") (pintype "passive"))
      (node (ref "C33") (pin "2") (pinfunction "2_2") (pintype "passive"))
      (node (ref "C34") (pin "2") (pinfunction "2_2") (pintype "passive"))
      (node (ref "C4") (pin "1") (pinfunction "1_1") (pintype "passive"))
      (node (ref "C5") (pin "1") (pinfunction "1_1") (pintype "passive"))
      (node (ref "C6") (pin "1") (pinfunction "1_1") (pintype "passive"))
      (node (ref "C7") (pin "1") (pinfunction "1_1") (pintype "passive"))
      (node (ref "C8") (pin "2") (pinfunction "2_2") (pintype "passive"))
      (node (ref "C9") (pin "2") (pinfunction "2_2") (pintype "passive"))
      (node (ref "J12") (pin "2") (pinfunction "2_2") (pintype "passive"))
      (node (ref "J3") (pin "1") (pinfunction "1_1") (pintype "passive"))
      (node (ref "J5") (pin "1") (pinfunction "1_1") (pintype "passive"))
      (node (ref "J7") (pin "1") (pinfunction "1_1") (pintype "passive"))
      (node (ref "J8") (pin "1") (pinfunction "1_1") (pintype "passive"))
      (node (ref "J8") (pin "2") (pinfunction "2_2") (pintype "passive"))
      (node (ref "J8") (pin "3") (pinfunction "3_3") (pintype "passive"))
      (node (ref "J8") (pin "4") (pinfunction "4_4") (pintype "passive"))
      (node (ref "J9") (pin "6") (pinfunction "6_6") (pintype "passive"))
      (node (ref "L2") (pin "1") (pinfunction "1_1") (pintype "passive"))
      (node (ref "R13") (pin "1") (pinfunction "1_1") (pintype "passive"))
      (node (ref "R14") (pin "1") (pinfunction "1_1") (pintype "passive"))
      (node (ref "R15") (pin "2") (pinfunction "2_2") (pintype "passive"))
      (node (ref "R16") (pin "1") (pinfunction "1_1") (pintype "passive"))
      (node (ref "R17") (pin "1") (pinfunction "1_1") (pintype "passive"))
      (node (ref "R18") (pin "1") (pinfunction "1_1") (pintype "passive"))
      (node (ref "R19") (pin "1") (pinfunction "1_1") (pintype "passive"))
      (node (ref "R2") (pin "2") (pinfunction "2_2") (pintype "passive"))
      (node (ref "R30") (pin "1") (pinfunction "1_1") (pintype "passive"))
      (node (ref "R32") (pin "2") (pinfunction "2_2") (pintype "passive"))
      (node (ref "R4") (pin "2") (pinfunction "2_2") (pintype "passive"))
      (node (ref "R6") (pin "2") (pinfunction "2_2") (pintype "passive"))
      (node (ref "R8") (pin "1") (pinfunction "1_1") (pintype "passive"))
      (node (ref "RP3") (pin "5") (pinfunction "5_5") (pintype "passive"))
      (node (ref "RP4") (pin "1") (pinfunction "1_1") (pintype "passive"))
      (node (ref "RP4") (pin "2") (pinfunction "2_2") (pintype "passive"))
      (node (ref "RP4") (pin "3") (pinfunction "3_3") (pintype "passive"))
      (node (ref "RP4") (pin "4") (pinfunction "4_4") (pintype "passive"))
      (node (ref "S1") (pin "5") (pinfunction "5_5") (pintype "passive"))
      (node (ref "S1") (pin "6") (pinfunction "6_6") (pintype "passive"))
      (node (ref "S1") (pin "7") (pinfunction "7_7") (pintype "passive"))
      (node (ref "S1") (pin "8") (pinfunction "8_8") (pintype "passive"))
      (node (ref "S2") (pin "1") (pinfunction "COMMON_1") (pintype "passive"))
      (node (ref "U1") (pin "8") (pinfunction "GND_8") (pintype "power_in"))
      (node (ref "U2") (pin "8") (pinfunction "GND_8") (pintype "power_in"))
      (node (ref "U3") (pin "12") (pinfunction "VSSA_12") (pintype "power_in"))
      (node (ref "U3") (pin "18") (pinfunction "VSS_4_18") (pintype "power_in"))
      (node (ref "U3") (pin "31") (pinfunction "VSS_1_31") (pintype "power_in"))
      (node (ref "U3") (pin "47") (pinfunction "VSS_2_47") (pintype "power_in"))
      (node (ref "U3") (pin "63") (pinfunction "VSS_3_63") (pintype "power_in"))
      (node (ref "U4") (pin "2") (pinfunction "GND_2") (pintype "passive"))
      (node (ref "U4") (pin "8") (pinfunction "S_8") (pintype "passive"))
      (node (ref "U5") (pin "10") (pinfunction "N.C._10") (pintype "passive"))
      (node (ref "U5") (pin "11") (pinfunction "N.C._11") (pintype "passive"))
      (node (ref "U5") (pin "12") (pinfunction "N.C._12") (pintype "passive"))
      (node (ref "U5") (pin "13") (pinfunction "GND_13") (pintype "passive"))
      (node (ref "U5") (pin "5") (pinfunction "N.C._5") (pintype "passive"))
      (node (ref "U5") (pin "6") (pinfunction "N.C._6") (pintype "passive"))
      (node (ref "U5") (pin "7") (pinfunction "N.C._7") (pintype "passive"))
      (node (ref "U5") (pin "8") (pinfunction "N.C._8") (pintype "passive"))
      (node (ref "U5") (pin "9") (pinfunction "N.C._9") (pintype "passive"))
      (node (ref "U6") (pin "14") (pinfunction "AGND_14") (pintype "passive"))
      (node (ref "U6") (pin "16") (pinfunction "AGND_16") (pintype "passive"))
      (node (ref "U6") (pin "19") (pinfunction "AGND_19") (pintype "passive"))
      (node (ref "U6") (pin "29") (pinfunction "GND_29") (pintype "passive"))
      (node (ref "U6") (pin "3") (pinfunction "AGND_3") (pintype "passive"))
      (node (ref "U6") (pin "48") (pinfunction "AGND_48") (pintype "passive"))
      (node (ref "VR1") (pin "2") (pinfunction "GND_2") (pintype "passive"))
      (node (ref "VR2") (pin "2") (pinfunction "GND_2") (pintype "passive"))
      (node (ref "VR3") (pin "1") (pinfunction "GND_1") (pintype "passive"))
      (node (ref "VR4") (pin "2") (pinfunction "GND_2") (pintype "passive"))
      (node (ref "VR5") (pin "1") (pinfunction "GND_1") (pintype "passive"))
    )
    (net (code "57") (name "Net-(*1-OFF)") (class "Default")
      (node (ref "*1") (pin "4") (pinfunction "OFF_4") (pintype "passive"))
      (node (ref "D1") (pin "K") (pinfunction "K_K") (pintype "passive"))
    )
    (net (code "58") (name "Net-(*1-ON)") (class "Default")
      (node (ref "*1") (pin "5") (pinfunction "ON_5") (pintype "passive"))
      (node (ref "D3") (pin "K") (pinfunction "K_K") (pintype "passive"))
    )
    (net (code "59") (name "Net-(D1-PadA)") (class "Default")
      (node (ref "D1") (pin "A") (pinfunction "A_A") (pintype "passive"))
      (node (ref "R7") (pin "2") (pinfunction "2_2") (pintype "passive"))
    )
    (net (code "60") (name "Net-(D2-A)") (class "Default")
      (node (ref "D2") (pin "1") (pinfunction "A_1") (pintype "passive"))
      (node (ref "Q3") (pin "3") (pinfunction "C_3") (pintype "passive"))
    )
    (net (code "61") (name "Net-(D3-PadA)") (class "Default")
      (node (ref "D3") (pin "A") (pinfunction "A_A") (pintype "passive"))
      (node (ref "R11") (pin "2") (pinfunction "2_2") (pintype "passive"))
    )
    (net (code "62") (name "Net-(D4-PadK)") (class "Default")
      (node (ref "D4") (pin "K") (pinfunction "K_K") (pintype "passive"))
      (node (ref "R13") (pin "2") (pinfunction "2_2") (pintype "passive"))
    )
    (net (code "63") (name "Net-(D5-PadK)") (class "Default")
      (node (ref "D5") (pin "K") (pinfunction "K_K") (pintype "passive"))
      (node (ref "R14") (pin "2") (pinfunction "2_2") (pintype "passive"))
    )
    (net (code "64") (name "Net-(D6-A)") (class "Default")
      (node (ref "D6") (pin "1") (pinfunction "A_1") (pintype "passive"))
      (node (ref "R10") (pin "2") (pinfunction "2_2") (pintype "passive"))
    )
    (net (code "65") (name "Net-(D7-PadK)") (class "Default")
      (node (ref "D7") (pin "K") (pinfunction "K_K") (pintype "passive"))
      (node (ref "R16") (pin "2") (pinfunction "2_2") (pintype "passive"))
    )
    (net (code "66") (name "Net-(D8-PadK)") (class "Default")
      (node (ref "D8") (pin "K") (pinfunction "K_K") (pintype "passive"))
      (node (ref "R17") (pin "2") (pinfunction "2_2") (pintype "passive"))
    )
    (net (code "67") (name "Net-(D9-PadK)") (class "Default")
      (node (ref "D9") (pin "K") (pinfunction "K_K") (pintype "passive"))
      (node (ref "R18") (pin "2") (pinfunction "2_2") (pintype "passive"))
    )
    (net (code "68") (name "Net-(D10-PadK)") (class "Default")
      (node (ref "D10") (pin "K") (pinfunction "K_K") (pintype "passive"))
      (node (ref "R19") (pin "2") (pinfunction "2_2") (pintype "passive"))
    )
    (net (code "69") (name "Net-(J10-GND-Pad1)") (class "Default")
      (node (ref "J10") (pin "1") (pinfunction "GND_1") (pintype "passive"))
      (node (ref "R11") (pin "1") (pinfunction "1_1") (pintype "passive"))
    )
    (net (code "70") (name "Net-(J13-CHS)") (class "Default")
      (node (ref "C28") (pin "2") (pinfunction "2_2") (pintype "passive"))
      (node (ref "C29") (pin "2") (pinfunction "2_2") (pintype "passive"))
      (node (ref "J13") (pin "13") (pinfunction "SHILD_13") (pintype "passive"))
      (node (ref "J13") (pin "14") (pinfunction "SHILD_14") (pintype "passive"))
      (node (ref "J13") (pin "8") (pinfunction "CHS_8") (pintype "passive"))
    )
    (net (code "71") (name "Net-(J13-D1-)") (class "Default")
      (node (ref "J13") (pin "10") (pinfunction "D1-_10") (pintype "passive"))
      (node (ref "R29") (pin "2") (pinfunction "2_2") (pintype "passive"))
    )
    (net (code "72") (name "Net-(J13-D2-)") (class "Default")
      (node (ref "J13") (pin "11") (pinfunction "D2-_11") (pintype "passive"))
      (node (ref "R31") (pin "2") (pinfunction "2_2") (pintype "passive"))
    )
    (net (code "73") (name "Net-(J13-RCT)") (class "Default")
      (node (ref "C30") (pin "2") (pinfunction "2_2") (pintype "passive"))
      (node (ref "J13") (pin "5") (pinfunction "RCT_5") (pintype "passive"))
      (node (ref "R27") (pin "1") (pinfunction "1_1") (pintype "passive"))
      (node (ref "R28") (pin "1") (pinfunction "1_1") (pintype "passive"))
    )
    (net (code "74") (name "Net-(J13-RDN)") (class "Default")
      (node (ref "C25") (pin "2") (pinfunction "2_2") (pintype "passive"))
      (node (ref "J13") (pin "6") (pinfunction "RDN_6") (pintype "passive"))
    )
    (net (code "75") (name "Net-(J13-RDP)") (class "Default")
      (node (ref "C22") (pin "2") (pinfunction "2_2") (pintype "passive"))
      (node (ref "J13") (pin "3") (pinfunction "RDP_3") (pintype "passive"))
    )
    (net (code "76") (name "Net-(J13-TCT)") (class "Default")
      (node (ref "C23") (pin "2") (pinfunction "2_2") (pintype "passive"))
      (node (ref "J13") (pin "4") (pinfunction "TCT_4") (pintype "passive"))
      (node (ref "R23") (pin "1") (pinfunction "1_1") (pintype "passive"))
    )
    (net (code "77") (name "Net-(P1-Pad1)") (class "Default")
      (node (ref "P1") (pin "1") (pinfunction "1_1") (pintype "passive"))
      (node (ref "R7") (pin "1") (pinfunction "1_1") (pintype "passive"))
    )
    (net (code "78") (name "Net-(Q1-B)") (class "Default")
      (node (ref "Q1") (pin "1") (pinfunction "B_1") (pintype "passive"))
      (node (ref "R3") (pin "2") (pinfunction "2_2") (pintype "passive"))
    )
    (net (code "79") (name "Net-(Q1-C)") (class "Default")
      (node (ref "J4") (pin "2") (pinfunction "2_2") (pintype "passive"))
      (node (ref "Q1") (pin "3") (pinfunction "C_3") (pintype "passive"))
    )
    (net (code "80") (name "Net-(Q1-E)") (class "Default")
      (node (ref "Q1") (pin "2") (pinfunction "E_2") (pintype "passive"))
      (node (ref "R4") (pin "1") (pinfunction "1_1") (pintype "passive"))
    )
    (net (code "81") (name "Net-(Q2-B)") (class "Default")
      (node (ref "Q2") (pin "1") (pinfunction "B_1") (pintype "passive"))
      (node (ref "R5") (pin "2") (pinfunction "2_2") (pintype "passive"))
    )
    (net (code "82") (name "Net-(Q2-C)") (class "Default")
      (node (ref "Q2") (pin "3") (pinfunction "C_3") (pintype "passive"))
      (node (ref "w1") (pin "2") (pintype "passive"))
    )
    (net (code "83") (name "Net-(Q2-E)") (class "Default")
      (node (ref "Q2") (pin "2") (pinfunction "E_2") (pintype "passive"))
      (node (ref "R6") (pin "1") (pinfunction "1_1") (pintype "passive"))
    )
    (net (code "84") (name "Net-(Q3-B)") (class "Default")
      (node (ref "Q3") (pin "1") (pinfunction "B_1") (pintype "passive"))
      (node (ref "R12") (pin "2") (pinfunction "2_2") (pintype "passive"))
    )
    (net (code "85") (name "Net-(Q3-E)") (class "Default")
      (node (ref "Q3") (pin "2") (pinfunction "E_2") (pintype "passive"))
      (node (ref "R15") (pin "1") (pinfunction "1_1") (pintype "passive"))
    )
    (net (code "86") (name "Net-(R32-Pad1)") (class "Default")
      (node (ref "R32") (pin "1") (pinfunction "1_1") (pintype "passive"))
      (node (ref "U6") (pin "23") (pinfunction "RSVD_23") (pintype "passive"))
    )
    (net (code "87") (name "Net-(RP3-Pad4)") (class "Default")
      (node (ref "RP3") (pin "4") (pinfunction "4_4") (pintype "passive"))
      (node (ref "U6") (pin "42") (pinfunction "RSVD_42") (pintype "passive"))
    )
    (net (code "88") (name "Net-(RP4-Pad5)") (class "Default")
      (node (ref "RP4") (pin "5") (pinfunction "5_5") (pintype "passive"))
      (node (ref "U6") (pin "41") (pinfunction "RSVD_41") (pintype "passive"))
    )
    (net (code "89") (name "Net-(RP4-Pad6)") (class "Default")
      (node (ref "RP4") (pin "6") (pinfunction "6_6") (pintype "passive"))
      (node (ref "U6") (pin "40") (pinfunction "RSVD_40") (pintype "passive"))
    )
    (net (code "90") (name "Net-(RP4-Pad7)") (class "Default")
      (node (ref "RP4") (pin "7") (pinfunction "7_7") (pintype "passive"))
      (node (ref "U6") (pin "39") (pinfunction "RSVD_39") (pintype "passive"))
    )
    (net (code "91") (name "Net-(RP4-Pad8)") (class "Default")
      (node (ref "RP4") (pin "8") (pinfunction "8_8") (pintype "passive"))
      (node (ref "U6") (pin "38") (pinfunction "RSVD_38") (pintype "passive"))
    )
    (net (code "92") (name "Net-(S2-NO)") (class "Default")
      (node (ref "C5") (pin "2") (pinfunction "2_2") (pintype "passive"))
      (node (ref "R9") (pin "2") (pinfunction "2_2") (pintype "passive"))
      (node (ref "S2") (pin "2") (pinfunction "NO_2") (pintype "passive"))
      (node (ref "U3") (pin "7") (pinfunction "NRST_7") (pintype "bidirectional"))
    )
    (net (code "93") (name "Net-(U1-OUT1)") (class "Default")
      (node (ref "J1") (pin "1") (pinfunction "1_1") (pintype "passive"))
      (node (ref "U1") (pin "16") (pinfunction "OUT1_16") (pintype "open_collector"))
    )
    (net (code "94") (name "Net-(U1-OUT2)") (class "Default")
      (node (ref "J1") (pin "2") (pinfunction "2_2") (pintype "passive"))
      (node (ref "U1") (pin "15") (pinfunction "OUT2_15") (pintype "open_collector"))
    )
    (net (code "95") (name "Net-(U1-OUT3)") (class "Default")
      (node (ref "J1") (pin "3") (pinfunction "3_3") (pintype "passive"))
      (node (ref "U1") (pin "14") (pinfunction "OUT3_14") (pintype "open_collector"))
    )
    (net (code "96") (name "Net-(U1-OUT4)") (class "Default")
      (node (ref "J1") (pin "4") (pinfunction "4_4") (pintype "passive"))
      (node (ref "U1") (pin "13") (pinfunction "OUT4_13") (pintype "open_collector"))
    )
    (net (code "97") (name "Net-(U2-OUT1)") (class "Default")
      (node (ref "J2") (pin "1") (pinfunction "1_1") (pintype "passive"))
      (node (ref "U2") (pin "16") (pinfunction "OUT1_16") (pintype "open_collector"))
    )
    (net (code "98") (name "Net-(U2-OUT2)") (class "Default")
      (node (ref "J2") (pin "2") (pinfunction "2_2") (pintype "passive"))
      (node (ref "U2") (pin "15") (pinfunction "OUT2_15") (pintype "open_collector"))
    )
    (net (code "99") (name "Net-(U2-OUT3)") (class "Default")
      (node (ref "J2") (pin "3") (pinfunction "3_3") (pintype "passive"))
      (node (ref "U2") (pin "14") (pinfunction "OUT3_14") (pintype "open_collector"))
    )
    (net (code "100") (name "Net-(U2-OUT4)") (class "Default")
      (node (ref "J2") (pin "4") (pinfunction "4_4") (pintype "passive"))
      (node (ref "U2") (pin "13") (pinfunction "OUT4_13") (pintype "open_collector"))
    )
    (net (code "101") (name "Net-(U3-BOOT0)") (class "Default")
      (node (ref "R8") (pin "2") (pinfunction "2_2") (pintype "passive"))
      (node (ref "U3") (pin "60") (pinfunction "BOOT0_60") (pintype "input"))
    )
    (net (code "102") (name "Net-(U3-OSC_IN{slash}PD0)") (class "Default")
      (node (ref "C3") (pin "2") (pinfunction "2_2") (pintype "passive"))
      (node (ref "U3") (pin "5") (pinfunction "OSC_IN/PD0_5") (pintype "input"))
      (node (ref "Y1") (pin "2") (pinfunction "OSC2_2") (pintype "passive"))
    )
    (net (code "103") (name "Net-(U3-OSC_OUT{slash}PD1)") (class "Default")
      (node (ref "C4") (pin "2") (pinfunction "2_2") (pintype "passive"))
      (node (ref "U3") (pin "6") (pinfunction "OSC_OUT/PD1_6") (pintype "output"))
      (node (ref "Y1") (pin "1") (pinfunction "OSC1_1") (pintype "passive"))
    )
    (net (code "104") (name "Net-(U3-PB2{slash}BOOT1)") (class "Default")
      (node (ref "R2") (pin "1") (pinfunction "1_1") (pintype "passive"))
      (node (ref "U3") (pin "28") (pinfunction "PB2/BOOT1_28") (pintype "bidirectional"))
    )
    (net (code "105") (name "Net-(U3-PC0)") (class "Default")
      (node (ref "RP1") (pin "8") (pinfunction "8_8") (pintype "passive"))
      (node (ref "S1") (pin "1") (pinfunction "1_1") (pintype "passive"))
      (node (ref "U3") (pin "8") (pinfunction "PC0_8") (pintype "bidirectional"))
    )
    (net (code "106") (name "Net-(U3-PC1)") (class "Default")
      (node (ref "RP1") (pin "7") (pinfunction "7_7") (pintype "passive"))
      (node (ref "S1") (pin "2") (pinfunction "2_2") (pintype "passive"))
      (node (ref "U3") (pin "9") (pinfunction "PC1_9") (pintype "bidirectional"))
    )
    (net (code "107") (name "Net-(U3-PC2)") (class "Default")
      (node (ref "RP1") (pin "6") (pinfunction "6_6") (pintype "passive"))
      (node (ref "S1") (pin "3") (pinfunction "3_3") (pintype "passive"))
      (node (ref "U3") (pin "10") (pinfunction "PC2_10") (pintype "bidirectional"))
    )
    (net (code "108") (name "Net-(U3-PC3)") (class "Default")
      (node (ref "RP1") (pin "5") (pinfunction "5_5") (pintype "passive"))
      (node (ref "S1") (pin "4") (pinfunction "4_4") (pintype "passive"))
      (node (ref "U3") (pin "11") (pinfunction "PC3_11") (pintype "bidirectional"))
    )
    (net (code "109") (name "Net-(U4-CANH)") (class "Default")
      (node (ref "J6") (pin "2") (pinfunction "2_2") (pintype "passive"))
      (node (ref "R1") (pin "1") (pinfunction "1_1") (pintype "passive"))
      (node (ref "U4") (pin "7") (pinfunction "CANH_7") (pintype "passive"))
    )
    (net (code "110") (name "Net-(U4-CANL)") (class "Default")
      (node (ref "J6") (pin "1") (pinfunction "1_1") (pintype "passive"))
      (node (ref "R1") (pin "2") (pinfunction "2_2") (pintype "passive"))
      (node (ref "U4") (pin "6") (pinfunction "CANL_6") (pintype "passive"))
    )
    (net (code "111") (name "Net-(U6-1V2O)") (class "Default")
      (node (ref "C33") (pin "1") (pinfunction "1_1") (pintype "passive"))
      (node (ref "U6") (pin "22") (pinfunction "1V2O_22") (pintype "passive"))
    )
    (net (code "112") (name "Net-(U6-EXRES1)") (class "Default")
      (node (ref "R30") (pin "2") (pinfunction "2_2") (pintype "passive"))
      (node (ref "U6") (pin "10") (pinfunction "EXRES1_10") (pintype "passive"))
    )
    (net (code "113") (name "Net-(U6-TOCAP)") (class "Default")
      (node (ref "C34") (pin "1") (pinfunction "1_1") (pintype "passive"))
      (node (ref "U6") (pin "20") (pinfunction "TOCAP_20") (pintype "passive"))
    )
    (net (code "114") (name "Net-(U6-XI{slash}CLCKIN)") (class "Default")
      (node (ref "C26") (pin "1") (pinfunction "1_1") (pintype "passive"))
      (node (ref "R26") (pin "1") (pinfunction "1_1") (pintype "passive"))
      (node (ref "U6") (pin "30") (pinfunction "XI/CLCKIN_30") (pintype "passive"))
      (node (ref "Y2") (pin "1") (pinfunction "OSC1_1") (pintype "passive"))
    )
    (net (code "115") (name "Net-(U6-XO)") (class "Default")
      (node (ref "C24") (pin "1") (pinfunction "1_1") (pintype "passive"))
      (node (ref "R26") (pin "2") (pinfunction "2_2") (pintype "passive"))
      (node (ref "U6") (pin "31") (pinfunction "XO_31") (pintype "passive"))
      (node (ref "Y2") (pin "3") (pinfunction "OSC2_3") (pintype "passive"))
    )
    (net (code "116") (name "unconnected-(J13-NC-Pad7)") (class "Default")
      (node (ref "J13") (pin "7") (pinfunction "NC_7") (pintype "passive"))
    )
    (net (code "117") (name "unconnected-(U1-IN5-Pad5)") (class "Default")
      (node (ref "U1") (pin "5") (pinfunction "IN5_5") (pintype "input"))
    )
    (net (code "118") (name "unconnected-(U1-IN6-Pad6)") (class "Default")
      (node (ref "U1") (pin "6") (pinfunction "IN6_6") (pintype "input"))
    )
    (net (code "119") (name "unconnected-(U1-IN7-Pad7)") (class "Default")
      (node (ref "U1") (pin "7") (pinfunction "IN7_7") (pintype "input"))
    )
    (net (code "120") (name "unconnected-(U1-OUT5-Pad12)") (class "Default")
      (node (ref "U1") (pin "12") (pinfunction "OUT5_12") (pintype "open_collector"))
    )
    (net (code "121") (name "unconnected-(U1-OUT6-Pad11)") (class "Default")
      (node (ref "U1") (pin "11") (pinfunction "OUT6_11") (pintype "open_collector"))
    )
    (net (code "122") (name "unconnected-(U1-OUT7-Pad10)") (class "Default")
      (node (ref "U1") (pin "10") (pinfunction "OUT7_10") (pintype "open_collector"))
    )
    (net (code "123") (name "unconnected-(U2-IN5-Pad5)") (class "Default")
      (node (ref "U2") (pin "5") (pinfunction "IN5_5") (pintype "input"))
    )
    (net (code "124") (name "unconnected-(U2-IN6-Pad6)") (class "Default")
      (node (ref "U2") (pin "6") (pinfunction "IN6_6") (pintype "input"))
    )
    (net (code "125") (name "unconnected-(U2-IN7-Pad7)") (class "Default")
      (node (ref "U2") (pin "7") (pinfunction "IN7_7") (pintype "input"))
    )
    (net (code "126") (name "unconnected-(U2-OUT5-Pad12)") (class "Default")
      (node (ref "U2") (pin "12") (pinfunction "OUT5_12") (pintype "open_collector"))
    )
    (net (code "127") (name "unconnected-(U2-OUT6-Pad11)") (class "Default")
      (node (ref "U2") (pin "11") (pinfunction "OUT6_11") (pintype "open_collector"))
    )
    (net (code "128") (name "unconnected-(U2-OUT7-Pad10)") (class "Default")
      (node (ref "U2") (pin "10") (pinfunction "OUT7_10") (pintype "open_collector"))
    )
    (net (code "129") (name "unconnected-(U3-PA0-WKUP-Pad14)") (class "Default")
      (node (ref "U3") (pin "14") (pinfunction "PA0-WKUP_14") (pintype "bidirectional"))
    )
    (net (code "130") (name "unconnected-(U3-PA15{slash}JTDI-Pad50)") (class "Default")
      (node (ref "U3") (pin "50") (pinfunction "PA15/JTDI_50") (pintype "bidirectional"))
    )
    (net (code "131") (name "unconnected-(U3-PB3{slash}JTDO-Pad55)") (class "Default")
      (node (ref "U3") (pin "55") (pinfunction "PB3/JTDO_55") (pintype "bidirectional"))
    )
    (net (code "132") (name "unconnected-(U3-PC13-TAMPER-RTC-Pad2)") (class "Default")
      (node (ref "U3") (pin "2") (pinfunction "PC13-TAMPER-RTC_2") (pintype "bidirectional"))
    )
    (net (code "133") (name "unconnected-(U3-PC14-OSC32_IN-Pad3)") (class "Default")
      (node (ref "U3") (pin "3") (pinfunction "PC14-OSC32_IN_3") (pintype "bidirectional"))
    )
    (net (code "134") (name "unconnected-(U3-PC15-OSC32_OUT-Pad4)") (class "Default")
      (node (ref "U3") (pin "4") (pinfunction "PC15-OSC32_OUT_4") (pintype "bidirectional"))
    )
    (net (code "135") (name "unconnected-(U3-PD2-Pad54)") (class "Default")
      (node (ref "U3") (pin "54") (pinfunction "PD2_54") (pintype "bidirectional"))
    )
    (net (code "136") (name "unconnected-(U4-n.c.-Pad5)") (class "Default")
      (node (ref "U4") (pin "5") (pinfunction "n.c._5") (pintype "passive"))
    )
    (net (code "137") (name "unconnected-(U5-~{RST}-Pad4)") (class "Default")
      (node (ref "U5") (pin "4") (pinfunction "~{RST}_4") (pintype "passive"))
    )
    (net (code "138") (name "unconnected-(U6-AGND-Pad9)") (class "Default")
      (node (ref "U6") (pin "9") (pinfunction "AGND_9") (pintype "passive"))
    )
    (net (code "139") (name "unconnected-(U6-AVDD-Pad8)") (class "Default")
      (node (ref "U6") (pin "8") (pinfunction "AVDD_8") (pintype "passive"))
    )
    (net (code "140") (name "unconnected-(U6-AVDD-Pad11)") (class "Default")
      (node (ref "U6") (pin "11") (pinfunction "AVDD_11") (pintype "passive"))
    )
    (net (code "141") (name "unconnected-(U6-DNC-Pad7)") (class "Default")
      (node (ref "U6") (pin "7") (pinfunction "DNC_7") (pintype "passive"))
    )
    (net (code "142") (name "unconnected-(U6-DUPLED-Pad26)") (class "Default")
      (node (ref "U6") (pin "26") (pinfunction "DUPLED_26") (pintype "passive"))
    )
    (net (code "143") (name "unconnected-(U6-NC-Pad12)") (class "Default")
      (node (ref "U6") (pin "12") (pinfunction "NC_12") (pintype "passive"))
    )
    (net (code "144") (name "unconnected-(U6-NC-Pad13)") (class "Default")
      (node (ref "U6") (pin "13") (pinfunction "NC_13") (pintype "passive"))
    )
    (net (code "145") (name "unconnected-(U6-NC-Pad46)") (class "Default")
      (node (ref "U6") (pin "46") (pinfunction "NC_46") (pintype "passive"))
    )
    (net (code "146") (name "unconnected-(U6-NC-Pad47)") (class "Default")
      (node (ref "U6") (pin "47") (pinfunction "NC_47") (pintype "passive"))
    )
    (net (code "147") (name "unconnected-(U6-SPDLED-Pad24)") (class "Default")
      (node (ref "U6") (pin "24") (pinfunction "SPDLED_24") (pintype "passive+no_connect"))
    )
    (net (code "148") (name "unconnected-(U6-VBG-Pad18)") (class "Default")
      (node (ref "U6") (pin "18") (pinfunction "VBG_18") (pintype "passive"))
    )
  )
)
